# design.net
KiCad netlist of a schematic drawn in Altium Designer
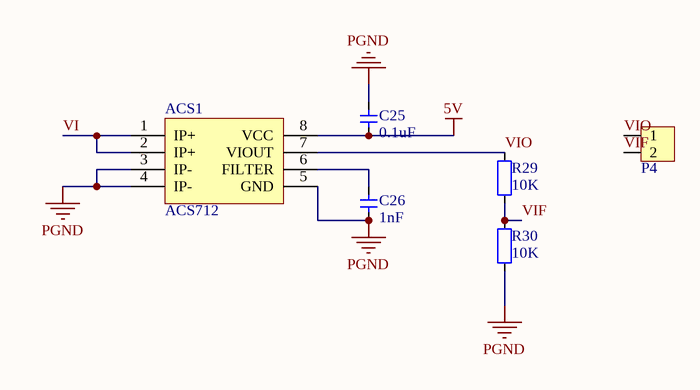
[diagram p0: 电流环.SchDoc]

(export (version "E")
  (design (tool "Eeschema 10.0.6"))
  (components
    (comp (ref "ACS1")
      (value "ACS712")
      (footprint "SOP8ACS712")
      (description "Sensor Current")
      (libsource (lib "SCH_IntegratedCircuit") (part "ACS712"))
    )
    (comp (ref "C25")
      (value "0.1uF")
      (footprint "CAP_0603")
      (description "Capacitor")
      (fields (field (name "Comment") "Cap_0603"))
      (libsource (lib "Integrated_Library") (part "Cap_0603"))
    )
    (comp (ref "C26")
      (value "1nF")
      (footprint "PCB_PassiveCap:CAP_0603")
      (description "Capacitor")
      (fields (field (name "Comment") "Cap_0603"))
      (libsource (lib "SCH_Passive") (part "Cap_0603"))
    )
    (comp (ref "P4")
      (value "HDR1x2_2.54")
      (footprint "HDR1X2_2.54_180")
      (description "Header")
      (libsource (lib "Integrated_Library") (part "HDR1x2_2.54"))
    )
    (comp (ref "R29")
      (value "10K")
      (footprint "RES_0603")
      (description "Resistor")
      (fields (field (name "Comment") "Res_0603"))
      (libsource (lib "Integrated_Library") (part "Res_0603"))
    )
    (comp (ref "R30")
      (value "10K")
      (footprint "RES_0603")
      (description "Resistor")
      (fields (field (name "Comment") "Res_0603"))
      (libsource (lib "Integrated_Library") (part "Res_0603"))
    )
  )
  (nets
    (net (code "1") (name "/VI") (class "Default")
      (node (ref "ACS1") (pin "1") (pinfunction "IP+_1") (pintype "passive"))
      (node (ref "ACS1") (pin "2") (pinfunction "IP+_2") (pintype "passive"))
    )
    (net (code "2") (name "/VIF") (class "Default")
      (node (ref "P4") (pin "2") (pinfunction "2_2") (pintype "passive"))
      (node (ref "R29") (pin "2") (pinfunction "2_2") (pintype "passive"))
      (node (ref "R30") (pin "1") (pinfunction "1_1") (pintype "passive"))
    )
    (net (code "3") (name "/VIO") (class "Default")
      (node (ref "ACS1") (pin "7") (pinfunction "VIOUT_7") (pintype "passive"))
      (node (ref "P4") (pin "1") (pinfunction "1_1") (pintype "passive"))
      (node (ref "R29") (pin "1") (pinfunction "1_1") (pintype "passive"))
    )
    (net (code "4") (name "5V") (class "Default")
      (node (ref "ACS1") (pin "8") (pinfunction "VCC_8") (pintype "passive"))
      (node (ref "C25") (pin "1") (pinfunction "1_1") (pintype "passive"))
    )
    (net (code "5") (name "Net-(ACS1-FILTER)") (class "Default")
      (node (ref "ACS1") (pin "6") (pinfunction "FILTER_6") (pintype "passive"))
      (node (ref "C26") (pin "2") (pinfunction "2_2") (pintype "passive"))
    )
    (net (code "6") (name "PGND") (class "Default")
      (node (ref "ACS1") (pin "3") (pinfunction "IP-_3") (pintype "passive"))
      (node (ref "ACS1") (pin "4") (pinfunction "IP-_4") (pintype "passive"))
      (node (ref "ACS1") (pin "5") (pinfunction "GND_5") (pintype "passive"))
      (node (ref "C25") (pin "2") (pinfunction "2_2") (pintype "passive"))
      (node (ref "C26") (pin "1") (pinfunction "1_1") (pintype "passive"))
      (node (ref "R30") (pin "2") (pinfunction "2_2") (pintype "passive"))
    )
  )
)
